# led_display_v1_0.net
KiCad netlist of a schematic drawn in EAGLE
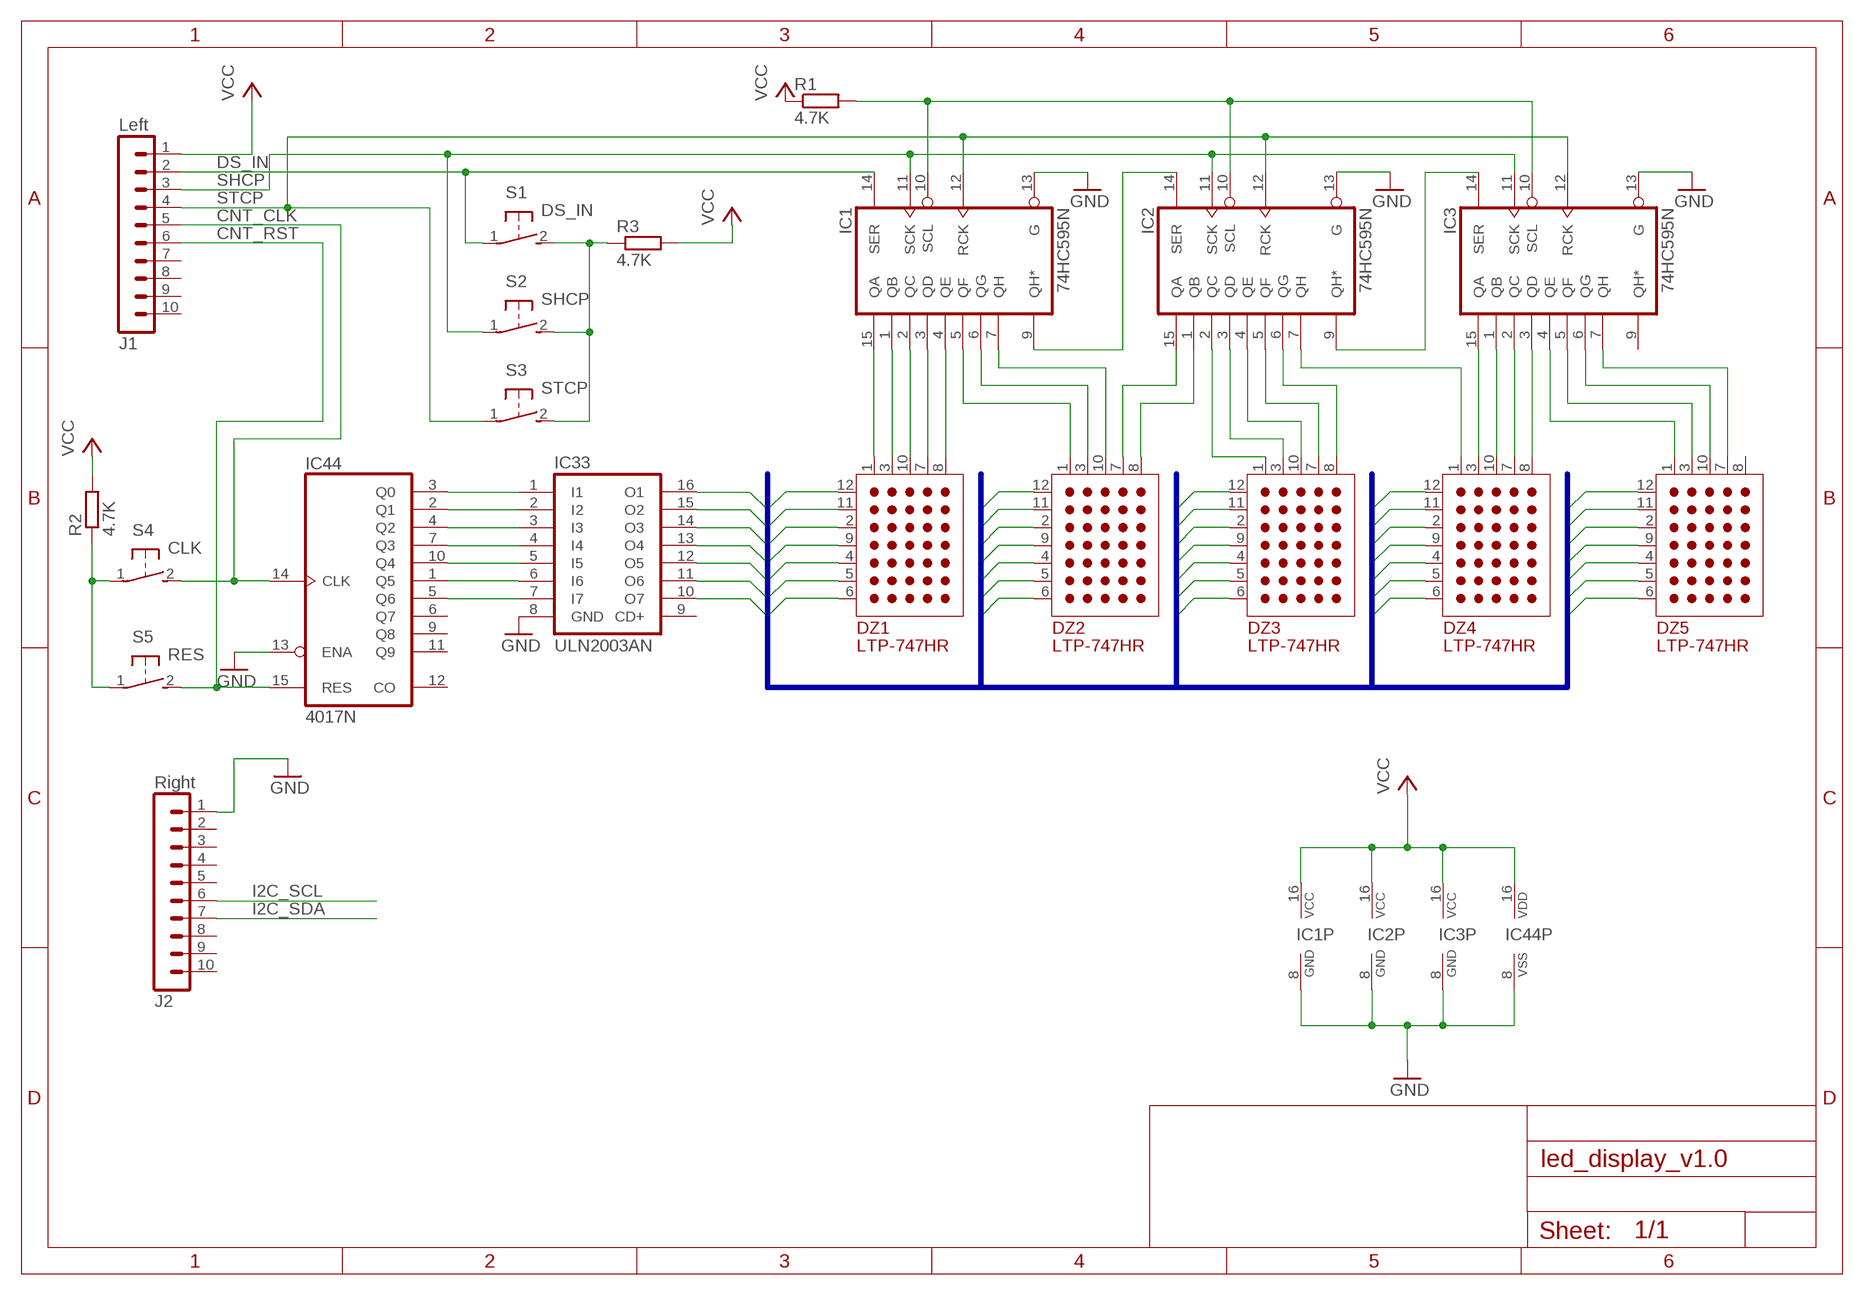
[diagram p0: schematic, sheet 1]

(export (version "E")
  (design (tool "Eeschema 10.0.6"))
  (components
    (comp (ref "DZ1")
      (value "LTP-747HR")
      (footprint "eagle-import:LTP-747HR")
      (libsource (lib "eagle-import") (part "LTP-747HR"))
    )
    (comp (ref "DZ2")
      (value "LTP-747HR")
      (footprint "eagle-import:LTP-747HR")
      (libsource (lib "eagle-import") (part "LTP-747HR"))
    )
    (comp (ref "DZ3")
      (value "LTP-747HR")
      (footprint "eagle-import:LTP-747HR")
      (libsource (lib "eagle-import") (part "LTP-747HR"))
    )
    (comp (ref "DZ4")
      (value "LTP-747HR")
      (footprint "eagle-import:LTP-747HR")
      (libsource (lib "eagle-import") (part "LTP-747HR"))
    )
    (comp (ref "DZ5")
      (value "LTP-747HR")
      (footprint "eagle-import:LTP-747HR")
      (libsource (lib "eagle-import") (part "LTP-747HR"))
    )
    (comp (ref "IC1")
      (value "74HC595N")
      (footprint "eagle-import:DIL16")
      (libsource (lib "eagle-import") (part "74595NHC"))
    )
    (comp (ref "IC2")
      (value "74HC595N")
      (footprint "eagle-import:DIL16")
      (libsource (lib "eagle-import") (part "74595NHC"))
    )
    (comp (ref "IC3")
      (value "74HC595N")
      (footprint "eagle-import:DIL16")
      (libsource (lib "eagle-import") (part "74595NHC"))
    )
    (comp (ref "IC33")
      (value "ULN2003AN")
      (footprint "eagle-import:DIL16")
      (libsource (lib "eagle-import") (part "ULN2003AN"))
    )
    (comp (ref "IC44")
      (value "4017N")
      (footprint "eagle-import:DIL16")
      (libsource (lib "eagle-import") (part "4017N"))
    )
    (comp (ref "J1")
      (value "Left")
      (footprint "eagle-import:MA10-1")
      (libsource (lib "eagle-import") (part "MA10-1"))
    )
    (comp (ref "J2")
      (value "Right")
      (footprint "eagle-import:MA10-1")
      (libsource (lib "eagle-import") (part "MA10-1"))
    )
    (comp (ref "R1")
      (value "4.7K")
      (footprint "eagle-import:0204V")
      (libsource (lib "eagle-import") (part "R-EU_0204/2V"))
    )
    (comp (ref "R2")
      (value "4.7K")
      (footprint "eagle-import:0204V")
      (libsource (lib "eagle-import") (part "R-EU_0204/2V"))
    )
    (comp (ref "R3")
      (value "4.7K")
      (footprint "eagle-import:0204V")
      (libsource (lib "eagle-import") (part "R-EU_0204/2V"))
    )
    (comp (ref "S1")
      (value "DS_IN")
      (footprint "eagle-import:B3F-31XX")
      (fields (field (name "MPN") "B3F-3100"))
      (libsource (lib "eagle-import") (part "31-XX"))
    )
    (comp (ref "S2")
      (value "SHCP")
      (footprint "eagle-import:B3F-31XX")
      (fields (field (name "MPN") "B3F-3100"))
      (libsource (lib "eagle-import") (part "31-XX"))
    )
    (comp (ref "S3")
      (value "STCP")
      (footprint "eagle-import:B3F-31XX")
      (fields (field (name "MPN") "B3F-3100"))
      (libsource (lib "eagle-import") (part "31-XX"))
    )
    (comp (ref "S4")
      (value "CLK")
      (footprint "eagle-import:B3F-31XX")
      (fields (field (name "MPN") "B3F-3100"))
      (libsource (lib "eagle-import") (part "31-XX"))
    )
    (comp (ref "S5")
      (value "RES")
      (footprint "eagle-import:B3F-31XX")
      (fields (field (name "MPN") "B3F-3100"))
      (libsource (lib "eagle-import") (part "31-XX"))
    )
  )
  (nets
    (net (code "1") (name "/CNT_CLK") (class "Default")
      (node (ref "IC44") (pin "14") (pinfunction "CLK_14") (pintype "input"))
      (node (ref "J1") (pin "5") (pinfunction "5_5") (pintype "passive"))
      (node (ref "S4") (pin "2") (pinfunction "S_2") (pintype "passive"))
    )
    (net (code "2") (name "/CNT_RST") (class "Default")
      (node (ref "IC44") (pin "15") (pinfunction "RES_15") (pintype "input"))
      (node (ref "J1") (pin "6") (pinfunction "6_6") (pintype "passive"))
      (node (ref "S5") (pin "2") (pinfunction "S_2") (pintype "passive"))
    )
    (net (code "3") (name "/DS_IN") (class "Default")
      (node (ref "IC1") (pin "14") (pinfunction "SER_14") (pintype "input"))
      (node (ref "J1") (pin "2") (pinfunction "2_2") (pintype "passive"))
      (node (ref "S1") (pin "1") (pinfunction "P_1") (pintype "passive"))
    )
    (net (code "4") (name "/I2C_SCL") (class "Default")
      (node (ref "J2") (pin "6") (pinfunction "6_6") (pintype "passive"))
    )
    (net (code "5") (name "/I2C_SDA") (class "Default")
      (node (ref "J2") (pin "7") (pinfunction "7_7") (pintype "passive"))
    )
    (net (code "6") (name "/R1") (class "Default")
      (node (ref "DZ1") (pin "12") (pinfunction "R1_12") (pintype "passive"))
      (node (ref "DZ2") (pin "12") (pinfunction "R1_12") (pintype "passive"))
      (node (ref "DZ3") (pin "12") (pinfunction "R1_12") (pintype "passive"))
      (node (ref "DZ4") (pin "12") (pinfunction "R1_12") (pintype "passive"))
      (node (ref "DZ5") (pin "12") (pinfunction "R1_12") (pintype "passive"))
      (node (ref "IC33") (pin "16") (pinfunction "O1_16") (pintype "open_collector"))
    )
    (net (code "7") (name "/R2") (class "Default")
      (node (ref "DZ1") (pin "11") (pinfunction "R2_11") (pintype "passive"))
      (node (ref "DZ2") (pin "11") (pinfunction "R2_11") (pintype "passive"))
      (node (ref "DZ3") (pin "11") (pinfunction "R2_11") (pintype "passive"))
      (node (ref "DZ4") (pin "11") (pinfunction "R2_11") (pintype "passive"))
      (node (ref "DZ5") (pin "11") (pinfunction "R2_11") (pintype "passive"))
      (node (ref "IC33") (pin "15") (pinfunction "O2_15") (pintype "open_collector"))
    )
    (net (code "8") (name "/R3") (class "Default")
      (node (ref "DZ1") (pin "2") (pinfunction "R3_2") (pintype "passive"))
      (node (ref "DZ2") (pin "2") (pinfunction "R3_2") (pintype "passive"))
      (node (ref "DZ3") (pin "2") (pinfunction "R3_2") (pintype "passive"))
      (node (ref "DZ4") (pin "2") (pinfunction "R3_2") (pintype "passive"))
      (node (ref "DZ5") (pin "2") (pinfunction "R3_2") (pintype "passive"))
      (node (ref "IC33") (pin "14") (pinfunction "O3_14") (pintype "open_collector"))
    )
    (net (code "9") (name "/R4") (class "Default")
      (node (ref "DZ1") (pin "9") (pinfunction "R4_9") (pintype "passive"))
      (node (ref "DZ2") (pin "9") (pinfunction "R4_9") (pintype "passive"))
      (node (ref "DZ3") (pin "9") (pinfunction "R4_9") (pintype "passive"))
      (node (ref "DZ4") (pin "9") (pinfunction "R4_9") (pintype "passive"))
      (node (ref "DZ5") (pin "9") (pinfunction "R4_9") (pintype "passive"))
      (node (ref "IC33") (pin "13") (pinfunction "O4_13") (pintype "open_collector"))
    )
    (net (code "10") (name "/R5") (class "Default")
      (node (ref "DZ1") (pin "4") (pinfunction "R5_4") (pintype "passive"))
      (node (ref "DZ2") (pin "4") (pinfunction "R5_4") (pintype "passive"))
      (node (ref "DZ3") (pin "4") (pinfunction "R5_4") (pintype "passive"))
      (node (ref "DZ4") (pin "4") (pinfunction "R5_4") (pintype "passive"))
      (node (ref "DZ5") (pin "4") (pinfunction "R5_4") (pintype "passive"))
      (node (ref "IC33") (pin "12") (pinfunction "O5_12") (pintype "open_collector"))
    )
    (net (code "11") (name "/R6") (class "Default")
      (node (ref "DZ1") (pin "5") (pinfunction "R6_5") (pintype "passive"))
      (node (ref "DZ2") (pin "5") (pinfunction "R6_5") (pintype "passive"))
      (node (ref "DZ3") (pin "5") (pinfunction "R6_5") (pintype "passive"))
      (node (ref "DZ4") (pin "5") (pinfunction "R6_5") (pintype "passive"))
      (node (ref "DZ5") (pin "5") (pinfunction "R6_5") (pintype "passive"))
      (node (ref "IC33") (pin "11") (pinfunction "O6_11") (pintype "open_collector"))
    )
    (net (code "12") (name "/R7") (class "Default")
      (node (ref "DZ1") (pin "6") (pinfunction "R7_6") (pintype "passive"))
      (node (ref "DZ2") (pin "6") (pinfunction "R7_6") (pintype "passive"))
      (node (ref "DZ3") (pin "6") (pinfunction "R7_6") (pintype "passive"))
      (node (ref "DZ4") (pin "6") (pinfunction "R7_6") (pintype "passive"))
      (node (ref "DZ5") (pin "6") (pinfunction "R7_6") (pintype "passive"))
      (node (ref "IC33") (pin "10") (pinfunction "O7_10") (pintype "open_collector"))
    )
    (net (code "13") (name "/SHCP") (class "Default")
      (node (ref "IC1") (pin "11") (pinfunction "SCK_11") (pintype "input"))
      (node (ref "IC2") (pin "11") (pinfunction "SCK_11") (pintype "input"))
      (node (ref "IC3") (pin "11") (pinfunction "SCK_11") (pintype "input"))
      (node (ref "J1") (pin "3") (pinfunction "3_3") (pintype "passive"))
      (node (ref "S2") (pin "1") (pinfunction "P_1") (pintype "passive"))
    )
    (net (code "14") (name "/STCP") (class "Default")
      (node (ref "IC1") (pin "12") (pinfunction "RCK_12") (pintype "input"))
      (node (ref "IC2") (pin "12") (pinfunction "RCK_12") (pintype "input"))
      (node (ref "IC3") (pin "12") (pinfunction "RCK_12") (pintype "input"))
      (node (ref "J1") (pin "4") (pinfunction "4_4") (pintype "passive"))
      (node (ref "S3") (pin "1") (pinfunction "P_1") (pintype "passive"))
    )
    (net (code "15") (name "GND") (class "Default")
      (node (ref "IC1") (pin "13") (pinfunction "G_13") (pintype "input"))
      (node (ref "IC1") (pin "8") (pinfunction "GND_8") (pintype "power_in"))
      (node (ref "IC2") (pin "13") (pinfunction "G_13") (pintype "input"))
      (node (ref "IC2") (pin "8") (pinfunction "GND_8") (pintype "power_in"))
      (node (ref "IC3") (pin "13") (pinfunction "G_13") (pintype "input"))
      (node (ref "IC3") (pin "8") (pinfunction "GND_8") (pintype "power_in"))
      (node (ref "IC33") (pin "8") (pinfunction "GND_8") (pintype "power_in"))
      (node (ref "IC44") (pin "13") (pinfunction "ENA_13") (pintype "input"))
      (node (ref "IC44") (pin "8") (pinfunction "VSS_8") (pintype "power_in"))
      (node (ref "J2") (pin "1") (pinfunction "1_1") (pintype "passive"))
    )
    (net (code "16") (name "Net-(DZ1-C1)") (class "Default")
      (node (ref "DZ1") (pin "1") (pinfunction "C1_1") (pintype "passive"))
      (node (ref "IC1") (pin "15") (pinfunction "QA_15") (pintype "tri_state"))
    )
    (net (code "17") (name "Net-(DZ1-C2)") (class "Default")
      (node (ref "DZ1") (pin "3") (pinfunction "C2_3") (pintype "passive"))
      (node (ref "IC1") (pin "1") (pinfunction "QB_1") (pintype "tri_state"))
    )
    (net (code "18") (name "Net-(DZ1-C3)") (class "Default")
      (node (ref "DZ1") (pin "10") (pinfunction "C3_10") (pintype "passive"))
      (node (ref "IC1") (pin "2") (pinfunction "QC_2") (pintype "tri_state"))
    )
    (net (code "19") (name "Net-(DZ1-C4)") (class "Default")
      (node (ref "DZ1") (pin "7") (pinfunction "C4_7") (pintype "passive"))
      (node (ref "IC1") (pin "3") (pinfunction "QD_3") (pintype "tri_state"))
    )
    (net (code "20") (name "Net-(DZ1-C5)") (class "Default")
      (node (ref "DZ1") (pin "8") (pinfunction "C5_8") (pintype "passive"))
      (node (ref "IC1") (pin "4") (pinfunction "QE_4") (pintype "tri_state"))
    )
    (net (code "21") (name "Net-(DZ2-C1)") (class "Default")
      (node (ref "DZ2") (pin "1") (pinfunction "C1_1") (pintype "passive"))
      (node (ref "IC1") (pin "5") (pinfunction "QF_5") (pintype "tri_state"))
    )
    (net (code "22") (name "Net-(DZ2-C2)") (class "Default")
      (node (ref "DZ2") (pin "3") (pinfunction "C2_3") (pintype "passive"))
      (node (ref "IC1") (pin "6") (pinfunction "QG_6") (pintype "tri_state"))
    )
    (net (code "23") (name "Net-(DZ2-C3)") (class "Default")
      (node (ref "DZ2") (pin "10") (pinfunction "C3_10") (pintype "passive"))
      (node (ref "IC1") (pin "7") (pinfunction "QH_7") (pintype "tri_state"))
    )
    (net (code "24") (name "Net-(DZ2-C4)") (class "Default")
      (node (ref "DZ2") (pin "7") (pinfunction "C4_7") (pintype "passive"))
      (node (ref "IC2") (pin "15") (pinfunction "QA_15") (pintype "tri_state"))
    )
    (net (code "25") (name "Net-(DZ2-C5)") (class "Default")
      (node (ref "DZ2") (pin "8") (pinfunction "C5_8") (pintype "passive"))
      (node (ref "IC2") (pin "1") (pinfunction "QB_1") (pintype "tri_state"))
    )
    (net (code "26") (name "Net-(DZ3-C1)") (class "Default")
      (node (ref "DZ3") (pin "1") (pinfunction "C1_1") (pintype "passive"))
      (node (ref "IC2") (pin "2") (pinfunction "QC_2") (pintype "tri_state"))
    )
    (net (code "27") (name "Net-(DZ3-C2)") (class "Default")
      (node (ref "DZ3") (pin "3") (pinfunction "C2_3") (pintype "passive"))
      (node (ref "IC2") (pin "3") (pinfunction "QD_3") (pintype "tri_state"))
    )
    (net (code "28") (name "Net-(DZ3-C3)") (class "Default")
      (node (ref "DZ3") (pin "10") (pinfunction "C3_10") (pintype "passive"))
      (node (ref "IC2") (pin "4") (pinfunction "QE_4") (pintype "tri_state"))
    )
    (net (code "29") (name "Net-(DZ3-C4)") (class "Default")
      (node (ref "DZ3") (pin "7") (pinfunction "C4_7") (pintype "passive"))
      (node (ref "IC2") (pin "5") (pinfunction "QF_5") (pintype "tri_state"))
    )
    (net (code "30") (name "Net-(DZ3-C5)") (class "Default")
      (node (ref "DZ3") (pin "8") (pinfunction "C5_8") (pintype "passive"))
      (node (ref "IC2") (pin "6") (pinfunction "QG_6") (pintype "tri_state"))
    )
    (net (code "31") (name "Net-(DZ4-C1)") (class "Default")
      (node (ref "DZ4") (pin "1") (pinfunction "C1_1") (pintype "passive"))
      (node (ref "IC2") (pin "7") (pinfunction "QH_7") (pintype "tri_state"))
    )
    (net (code "32") (name "Net-(DZ4-C2)") (class "Default")
      (node (ref "DZ4") (pin "3") (pinfunction "C2_3") (pintype "passive"))
      (node (ref "IC3") (pin "15") (pinfunction "QA_15") (pintype "tri_state"))
    )
    (net (code "33") (name "Net-(DZ4-C3)") (class "Default")
      (node (ref "DZ4") (pin "10") (pinfunction "C3_10") (pintype "passive"))
      (node (ref "IC3") (pin "1") (pinfunction "QB_1") (pintype "tri_state"))
    )
    (net (code "34") (name "Net-(DZ4-C4)") (class "Default")
      (node (ref "DZ4") (pin "7") (pinfunction "C4_7") (pintype "passive"))
      (node (ref "IC3") (pin "2") (pinfunction "QC_2") (pintype "tri_state"))
    )
    (net (code "35") (name "Net-(DZ4-C5)") (class "Default")
      (node (ref "DZ4") (pin "8") (pinfunction "C5_8") (pintype "passive"))
      (node (ref "IC3") (pin "3") (pinfunction "QD_3") (pintype "tri_state"))
    )
    (net (code "36") (name "Net-(DZ5-C1)") (class "Default")
      (node (ref "DZ5") (pin "1") (pinfunction "C1_1") (pintype "passive"))
      (node (ref "IC3") (pin "4") (pinfunction "QE_4") (pintype "tri_state"))
    )
    (net (code "37") (name "Net-(DZ5-C2)") (class "Default")
      (node (ref "DZ5") (pin "3") (pinfunction "C2_3") (pintype "passive"))
      (node (ref "IC3") (pin "5") (pinfunction "QF_5") (pintype "tri_state"))
    )
    (net (code "38") (name "Net-(DZ5-C3)") (class "Default")
      (node (ref "DZ5") (pin "10") (pinfunction "C3_10") (pintype "passive"))
      (node (ref "IC3") (pin "6") (pinfunction "QG_6") (pintype "tri_state"))
    )
    (net (code "39") (name "Net-(DZ5-C4)") (class "Default")
      (node (ref "DZ5") (pin "7") (pinfunction "C4_7") (pintype "passive"))
      (node (ref "IC3") (pin "7") (pinfunction "QH_7") (pintype "tri_state"))
    )
    (net (code "40") (name "Net-(IC1A-QH*)") (class "Default")
      (node (ref "IC1") (pin "9") (pinfunction "QH*_9") (pintype "tri_state"))
      (node (ref "IC2") (pin "14") (pinfunction "SER_14") (pintype "input"))
    )
    (net (code "41") (name "Net-(IC1A-SCL)") (class "Default")
      (node (ref "IC1") (pin "10") (pinfunction "SCL_10") (pintype "input"))
      (node (ref "IC2") (pin "10") (pinfunction "SCL_10") (pintype "input"))
      (node (ref "IC3") (pin "10") (pinfunction "SCL_10") (pintype "input"))
      (node (ref "R1") (pin "2") (pinfunction "2_2") (pintype "passive"))
    )
    (net (code "42") (name "Net-(IC2A-QH*)") (class "Default")
      (node (ref "IC2") (pin "9") (pinfunction "QH*_9") (pintype "tri_state"))
      (node (ref "IC3") (pin "14") (pinfunction "SER_14") (pintype "input"))
    )
    (net (code "43") (name "Net-(IC33-I1)") (class "Default")
      (node (ref "IC33") (pin "1") (pinfunction "I1_1") (pintype "input"))
      (node (ref "IC44") (pin "3") (pinfunction "Q0_3") (pintype "output"))
    )
    (net (code "44") (name "Net-(IC33-I2)") (class "Default")
      (node (ref "IC33") (pin "2") (pinfunction "I2_2") (pintype "input"))
      (node (ref "IC44") (pin "2") (pinfunction "Q1_2") (pintype "output"))
    )
    (net (code "45") (name "Net-(IC33-I3)") (class "Default")
      (node (ref "IC33") (pin "3") (pinfunction "I3_3") (pintype "input"))
      (node (ref "IC44") (pin "4") (pinfunction "Q2_4") (pintype "output"))
    )
    (net (code "46") (name "Net-(IC33-I4)") (class "Default")
      (node (ref "IC33") (pin "4") (pinfunction "I4_4") (pintype "input"))
      (node (ref "IC44") (pin "7") (pinfunction "Q3_7") (pintype "output"))
    )
    (net (code "47") (name "Net-(IC33-I5)") (class "Default")
      (node (ref "IC33") (pin "5") (pinfunction "I5_5") (pintype "input"))
      (node (ref "IC44") (pin "10") (pinfunction "Q4_10") (pintype "output"))
    )
    (net (code "48") (name "Net-(IC33-I6)") (class "Default")
      (node (ref "IC33") (pin "6") (pinfunction "I6_6") (pintype "input"))
      (node (ref "IC44") (pin "1") (pinfunction "Q5_1") (pintype "output"))
    )
    (net (code "49") (name "Net-(IC33-I7)") (class "Default")
      (node (ref "IC33") (pin "7") (pinfunction "I7_7") (pintype "input"))
      (node (ref "IC44") (pin "5") (pinfunction "Q6_5") (pintype "output"))
    )
    (net (code "50") (name "Net-(S1-S)") (class "Default")
      (node (ref "R3") (pin "1") (pinfunction "1_1") (pintype "passive"))
      (node (ref "S1") (pin "2") (pinfunction "S_2") (pintype "passive"))
      (node (ref "S2") (pin "2") (pinfunction "S_2") (pintype "passive"))
      (node (ref "S3") (pin "2") (pinfunction "S_2") (pintype "passive"))
    )
    (net (code "51") (name "Net-(S4-P)") (class "Default")
      (node (ref "R2") (pin "1") (pinfunction "1_1") (pintype "passive"))
      (node (ref "S4") (pin "1") (pinfunction "P_1") (pintype "passive"))
      (node (ref "S5") (pin "1") (pinfunction "P_1") (pintype "passive"))
    )
    (net (code "52") (name "VCC") (class "Default")
      (node (ref "IC1") (pin "16") (pinfunction "VCC_16") (pintype "power_in"))
      (node (ref "IC2") (pin "16") (pinfunction "VCC_16") (pintype "power_in"))
      (node (ref "IC3") (pin "16") (pinfunction "VCC_16") (pintype "power_in"))
      (node (ref "IC44") (pin "16") (pinfunction "VDD_16") (pintype "power_in"))
      (node (ref "J1") (pin "1") (pinfunction "1_1") (pintype "passive"))
      (node (ref "R1") (pin "1") (pinfunction "1_1") (pintype "passive"))
      (node (ref "R2") (pin "2") (pinfunction "2_2") (pintype "passive"))
      (node (ref "R3") (pin "2") (pinfunction "2_2") (pintype "passive"))
    )
    (net (code "53") (name "unconnected-(DZ5-C5-Pad8)") (class "Default")
      (node (ref "DZ5") (pin "8") (pinfunction "C5_8") (pintype "passive"))
    )
    (net (code "54") (name "unconnected-(IC3A-QH*-Pad9)") (class "Default")
      (node (ref "IC3") (pin "9") (pinfunction "QH*_9") (pintype "tri_state"))
    )
    (net (code "55") (name "unconnected-(IC33-CD+-Pad9)") (class "Default")
      (node (ref "IC33") (pin "9") (pinfunction "CD+_9") (pintype "passive"))
    )
    (net (code "56") (name "unconnected-(IC44A-CO-Pad12)") (class "Default")
      (node (ref "IC44") (pin "12") (pinfunction "CO_12") (pintype "output"))
    )
    (net (code "57") (name "unconnected-(IC44A-Q7-Pad6)") (class "Default")
      (node (ref "IC44") (pin "6") (pinfunction "Q7_6") (pintype "output"))
    )
    (net (code "58") (name "unconnected-(IC44A-Q8-Pad9)") (class "Default")
      (node (ref "IC44") (pin "9") (pinfunction "Q8_9") (pintype "output"))
    )
    (net (code "59") (name "unconnected-(IC44A-Q9-Pad11)") (class "Default")
      (node (ref "IC44") (pin "11") (pinfunction "Q9_11") (pintype "output"))
    )
    (net (code "60") (name "unconnected-(J1-Pad7)") (class "Default")
      (node (ref "J1") (pin "7") (pinfunction "7_7") (pintype "passive"))
    )
    (net (code "61") (name "unconnected-(J1-Pad8)") (class "Default")
      (node (ref "J1") (pin "8") (pinfunction "8_8") (pintype "passive"))
    )
    (net (code "62") (name "unconnected-(J1-Pad9)") (class "Default")
      (node (ref "J1") (pin "9") (pinfunction "9_9") (pintype "passive"))
    )
    (net (code "63") (name "unconnected-(J1-Pad10)") (class "Default")
      (node (ref "J1") (pin "10") (pinfunction "10_10") (pintype "passive"))
    )
    (net (code "64") (name "unconnected-(J2-Pad2)") (class "Default")
      (node (ref "J2") (pin "2") (pinfunction "2_2") (pintype "passive"))
    )
    (net (code "65") (name "unconnected-(J2-Pad3)") (class "Default")
      (node (ref "J2") (pin "3") (pinfunction "3_3") (pintype "passive"))
    )
    (net (code "66") (name "unconnected-(J2-Pad4)") (class "Default")
      (node (ref "J2") (pin "4") (pinfunction "4_4") (pintype "passive"))
    )
    (net (code "67") (name "unconnected-(J2-Pad5)") (class "Default")
      (node (ref "J2") (pin "5") (pinfunction "5_5") (pintype "passive"))
    )
    (net (code "68") (name "unconnected-(J2-Pad8)") (class "Default")
      (node (ref "J2") (pin "8") (pinfunction "8_8") (pintype "passive"))
    )
    (net (code "69") (name "unconnected-(J2-Pad9)") (class "Default")
      (node (ref "J2") (pin "9") (pinfunction "9_9") (pintype "passive"))
    )
    (net (code "70") (name "unconnected-(J2-Pad10)") (class "Default")
      (node (ref "J2") (pin "10") (pinfunction "10_10") (pintype "passive"))
    )
  )
)
